# GimmeSoul.net
KiCad netlist of a schematic drawn in EAGLE
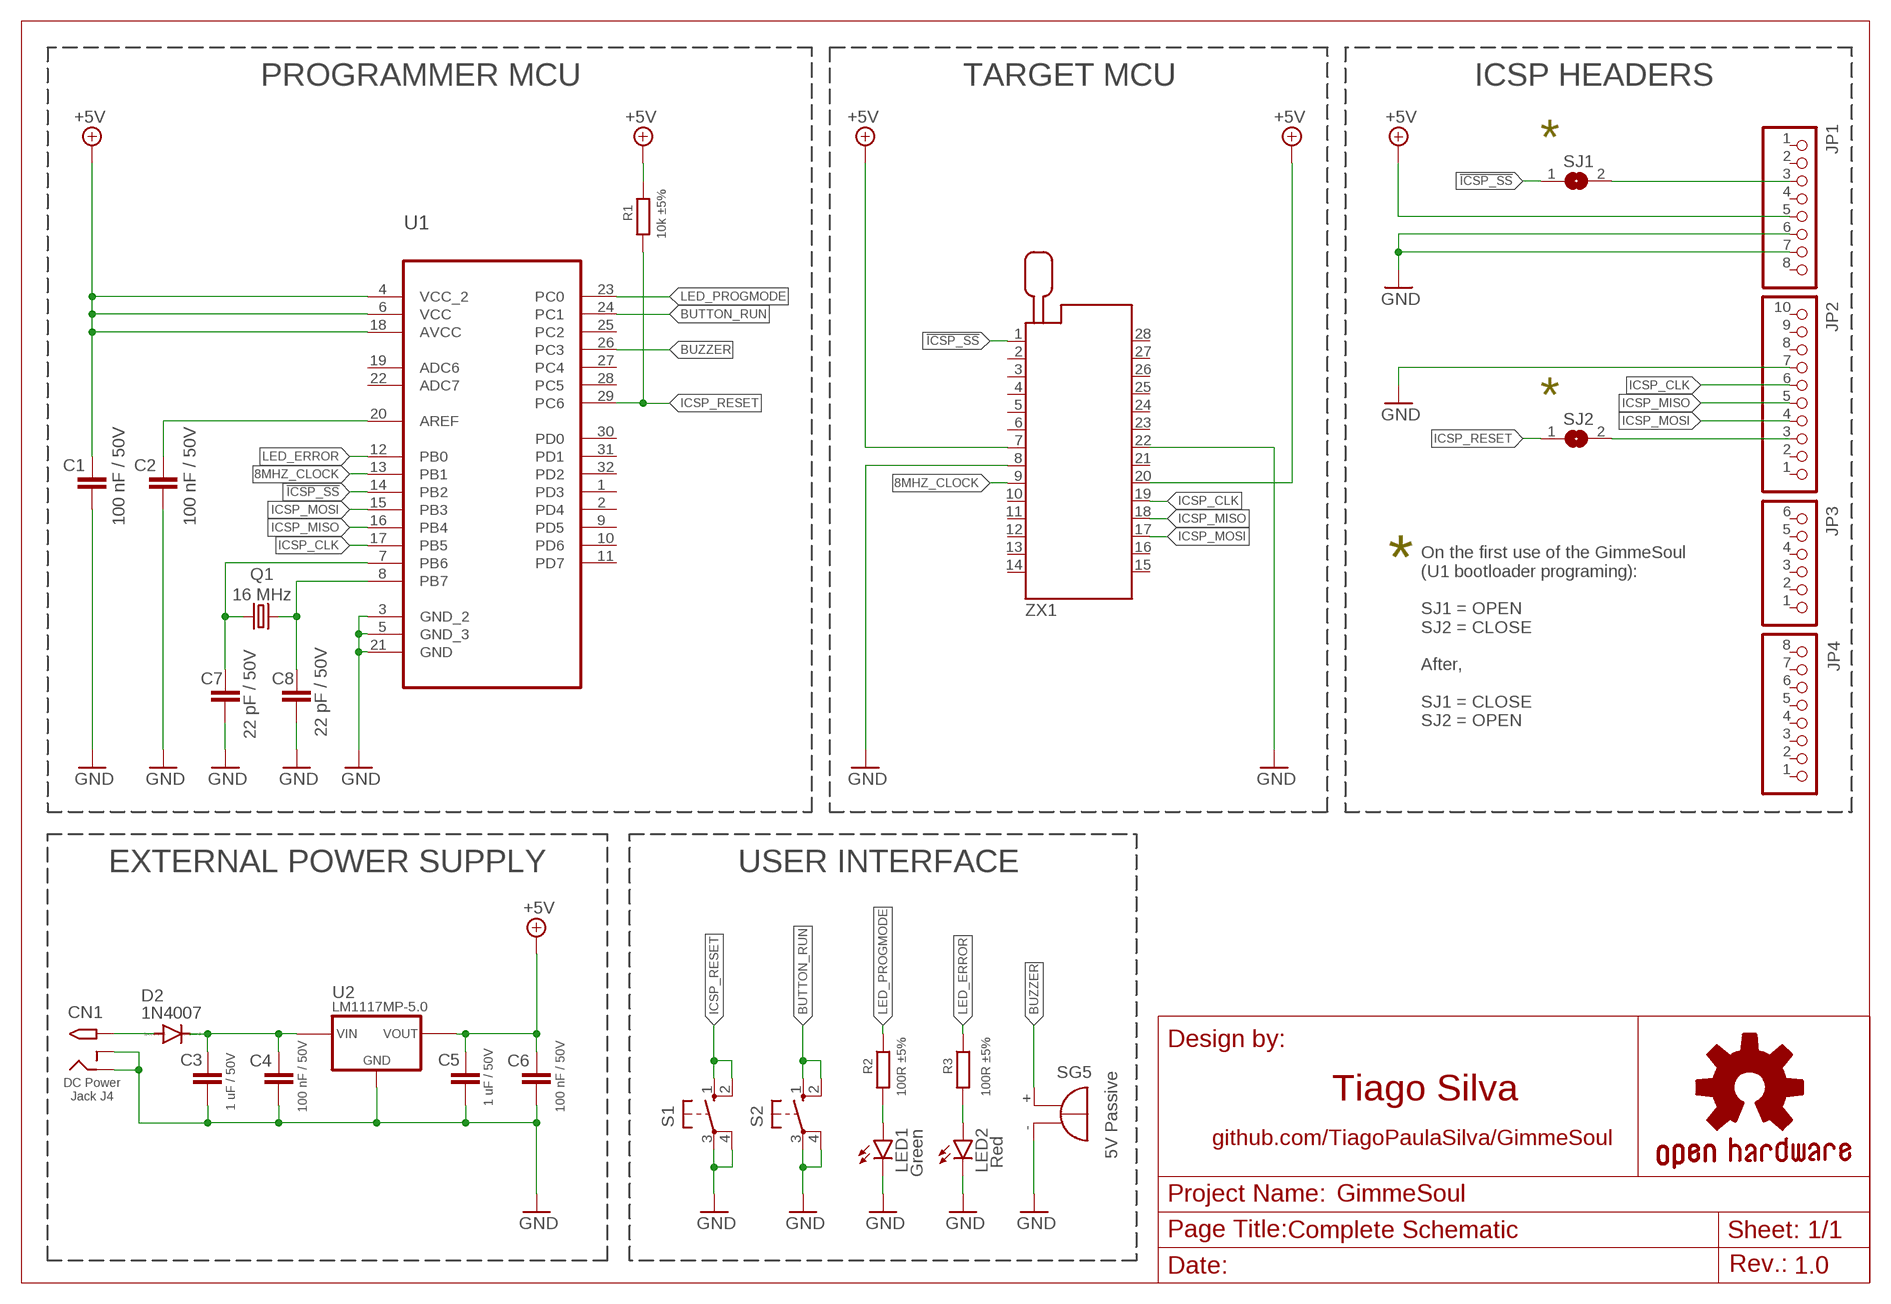
[diagram p0: schematic, sheet 1]

(export (version "E")
  (design (tool "Eeschema 10.0.6"))
  (components
    (comp (ref "C1")
      (value "100 nF / 50V")
      (footprint "eagle-import:C0805")
      (libsource (lib "eagle-import") (part "C-EUC0805"))
    )
    (comp (ref "C2")
      (value "100 nF / 50V")
      (footprint "eagle-import:C0805")
      (libsource (lib "eagle-import") (part "C-EUC0805"))
    )
    (comp (ref "C3")
      (value "1 uF / 50V")
      (footprint "eagle-import:C0805")
      (libsource (lib "eagle-import") (part "C-EUC0805"))
    )
    (comp (ref "C4")
      (value "100 nF / 50V")
      (footprint "eagle-import:C0805")
      (libsource (lib "eagle-import") (part "C-EUC0805"))
    )
    (comp (ref "C5")
      (value "1 uF / 50V")
      (footprint "eagle-import:C0805")
      (libsource (lib "eagle-import") (part "C-EUC0805"))
    )
    (comp (ref "C6")
      (value "100 nF / 50V")
      (footprint "eagle-import:C0805")
      (libsource (lib "eagle-import") (part "C-EUC0805"))
    )
    (comp (ref "C7")
      (value "22 pF / 50V")
      (footprint "eagle-import:C0805")
      (libsource (lib "eagle-import") (part "C-EUC0805"))
    )
    (comp (ref "C8")
      (value "22 pF / 50V")
      (footprint "eagle-import:C0805")
      (libsource (lib "eagle-import") (part "C-EUC0805"))
    )
    (comp (ref "CN1")
      (value "2.1MMJACKTHM")
      (footprint "eagle-import:PJ-102A")
      (libsource (lib "eagle-import") (part "2.1MMJACKTHM"))
    )
    (comp (ref "D2")
      (value "1N4007")
      (footprint "eagle-import:SOD123")
      (libsource (lib "eagle-import") (part "DIODE-SOD123"))
    )
    (comp (ref "JP1")
      (value "PINHD-1X8")
      (footprint "eagle-import:1X08")
      (libsource (lib "eagle-import") (part "PINHD-1X8"))
    )
    (comp (ref "JP2")
      (value "PINHD-1X10_ARD")
      (footprint "eagle-import:1X10")
      (libsource (lib "eagle-import") (part "PINHD-1X10_ARD"))
    )
    (comp (ref "JP3")
      (value "PINHD-1X6")
      (footprint "eagle-import:1X06")
      (libsource (lib "eagle-import") (part "PINHD-1X6"))
    )
    (comp (ref "JP4")
      (value "PINHD-1X8")
      (footprint "eagle-import:1X08")
      (libsource (lib "eagle-import") (part "PINHD-1X8"))
    )
    (comp (ref "LED1")
      (value "Green")
      (footprint "eagle-import:LED5MM")
      (libsource (lib "eagle-import") (part "LED5MM"))
    )
    (comp (ref "LED2")
      (value "Red")
      (footprint "eagle-import:LED5MM")
      (libsource (lib "eagle-import") (part "LED5MM"))
    )
    (comp (ref "Q1")
      (value "16 MHz")
      (footprint "eagle-import:HC49_S")
      (libsource (lib "eagle-import") (part "CRYSTALHC49S"))
    )
    (comp (ref "R1")
      (value "10k ±5%")
      (footprint "eagle-import:R0805")
      (libsource (lib "eagle-import") (part "R-EU_R0805"))
    )
    (comp (ref "R2")
      (value "100R ±5%")
      (footprint "eagle-import:R0805")
      (libsource (lib "eagle-import") (part "R-EU_R0805"))
    )
    (comp (ref "R3")
      (value "100R ±5%")
      (footprint "eagle-import:R0805")
      (libsource (lib "eagle-import") (part "R-EU_R0805"))
    )
    (comp (ref "S1")
      (value "10-XX")
      (footprint "eagle-import:B3F-10XX")
      (fields (field (name "MPN") "B3F-1000"))
      (libsource (lib "eagle-import") (part "10-XX"))
    )
    (comp (ref "S2")
      (value "10-XX")
      (footprint "eagle-import:B3F-10XX")
      (fields (field (name "MPN") "B3F-1000"))
      (libsource (lib "eagle-import") (part "10-XX"))
    )
    (comp (ref "SG5")
      (value "5V Passive")
      (footprint "eagle-import:F_QMBIII")
      (libsource (lib "eagle-import") (part "F/QMBIII"))
    )
    (comp (ref "SJ1") (value "SJ") (footprint "eagle-import:SJ") (libsource (lib "eagle-import") (part "SJ")))
    (comp (ref "SJ2") (value "SJ") (footprint "eagle-import:SJ") (libsource (lib "eagle-import") (part "SJ")))
    (comp (ref "U1")
      (value "ATMEGA328P-AU")
      (footprint "eagle-import:QFP80P900X900X120-32N")
      (libsource (lib "eagle-import") (part "ATMEGA328P-AU"))
    )
    (comp (ref "U2")
      (value "LM1117MP-5.0")
      (footprint "eagle-import:SOT223")
      (fields (field (name "MF") "Texas Instruments") (field (name "MP") "REG1117"))
      (libsource (lib "eagle-import") (part "REG1117"))
    )
    (comp (ref "ZX1")
      (value "228-4817-00-0602J")
      (footprint "eagle-import:228-4817-00-0602J")
      (fields (field (name "MF") "3M"))
      (libsource (lib "eagle-import") (part "228-?00-0602J4817-"))
    )
  )
  (nets
    (net (code "1") (name "+5V") (class "Default")
      (node (ref "C1") (pin "2") (pinfunction "2_2") (pintype "passive"))
      (node (ref "C5") (pin "1") (pinfunction "1_1") (pintype "passive"))
      (node (ref "C6") (pin "1") (pinfunction "1_1") (pintype "passive"))
      (node (ref "JP1") (pin "5") (pinfunction "5_5") (pintype "passive"))
      (node (ref "R1") (pin "1") (pinfunction "1_1") (pintype "passive"))
      (node (ref "U1") (pin "18") (pinfunction "AVCC_18") (pintype "power_in"))
      (node (ref "U1") (pin "4") (pinfunction "VCC_2_4") (pintype "power_in"))
      (node (ref "U1") (pin "6") (pinfunction "VCC_6") (pintype "power_in"))
      (node (ref "U2") (pin "2") (pinfunction "VOUT_2") (pintype "output"))
      (node (ref "U2") (pin "4") (pinfunction "VOUT_4") (pintype "output"))
      (node (ref "ZX1") (pin "20") (pinfunction "20_20") (pintype "passive"))
      (node (ref "ZX1") (pin "7") (pinfunction "7_7") (pintype "passive"))
    )
    (net (code "2") (name "/~{ICSP_SS}") (class "Default")
      (node (ref "SJ1") (pin "1") (pinfunction "1_1") (pintype "passive"))
      (node (ref "U1") (pin "14") (pinfunction "PB2_14") (pintype "bidirectional"))
      (node (ref "ZX1") (pin "1") (pinfunction "1_1") (pintype "passive"))
    )
    (net (code "3") (name "8MHZ_CLOCK") (class "Default")
      (node (ref "U1") (pin "13") (pinfunction "PB1_13") (pintype "bidirectional"))
      (node (ref "ZX1") (pin "9") (pinfunction "9_9") (pintype "passive"))
    )
    (net (code "4") (name "BUTTON_RUN") (class "Default")
      (node (ref "S2") (pin "1") (pinfunction "S_1") (pintype "passive"))
      (node (ref "S2") (pin "2") (pinfunction "S1_2") (pintype "passive"))
      (node (ref "U1") (pin "24") (pinfunction "PC1_24") (pintype "bidirectional"))
    )
    (net (code "5") (name "BUZZER") (class "Default")
      (node (ref "SG5") (pin "+") (pinfunction "-_+") (pintype "passive"))
      (node (ref "U1") (pin "26") (pinfunction "PC3_26") (pintype "bidirectional"))
    )
    (net (code "6") (name "GND") (class "Default")
      (node (ref "C1") (pin "1") (pinfunction "1_1") (pintype "passive"))
      (node (ref "C2") (pin "1") (pinfunction "1_1") (pintype "passive"))
      (node (ref "C3") (pin "2") (pinfunction "2_2") (pintype "passive"))
      (node (ref "C4") (pin "2") (pinfunction "2_2") (pintype "passive"))
      (node (ref "C5") (pin "2") (pinfunction "2_2") (pintype "passive"))
      (node (ref "C6") (pin "2") (pinfunction "2_2") (pintype "passive"))
      (node (ref "C7") (pin "1") (pinfunction "1_1") (pintype "passive"))
      (node (ref "C8") (pin "1") (pinfunction "1_1") (pintype "passive"))
      (node (ref "CN1") (pin "RING") (pinfunction "RING_RING") (pintype "bidirectional"))
      (node (ref "CN1") (pin "RING_SW") (pinfunction "RING_SW_RING_SW") (pintype "bidirectional"))
      (node (ref "JP1") (pin "6") (pinfunction "6_6") (pintype "passive"))
      (node (ref "JP1") (pin "7") (pinfunction "7_7") (pintype "passive"))
      (node (ref "JP2") (pin "7") (pinfunction "7_7") (pintype "passive"))
      (node (ref "LED1") (pin "K") (pinfunction "C_K") (pintype "passive"))
      (node (ref "LED2") (pin "K") (pinfunction "C_K") (pintype "passive"))
      (node (ref "S1") (pin "3") (pinfunction "P_3") (pintype "passive"))
      (node (ref "S1") (pin "4") (pinfunction "P1_4") (pintype "passive"))
      (node (ref "S2") (pin "3") (pinfunction "P_3") (pintype "passive"))
      (node (ref "S2") (pin "4") (pinfunction "P1_4") (pintype "passive"))
      (node (ref "SG5") (pin "-") (pinfunction "+_-") (pintype "passive"))
      (node (ref "U1") (pin "21") (pinfunction "GND_21") (pintype "passive"))
      (node (ref "U1") (pin "3") (pinfunction "GND_2_3") (pintype "passive"))
      (node (ref "U1") (pin "5") (pinfunction "GND_3_5") (pintype "passive"))
      (node (ref "U2") (pin "1") (pinfunction "GND_1") (pintype "power_in"))
      (node (ref "ZX1") (pin "22") (pinfunction "22_22") (pintype "passive"))
      (node (ref "ZX1") (pin "8") (pinfunction "8_8") (pintype "passive"))
    )
    (net (code "7") (name "ICSP_CLK") (class "Default")
      (node (ref "JP2") (pin "6") (pinfunction "6_6") (pintype "passive"))
      (node (ref "U1") (pin "17") (pinfunction "PB5_17") (pintype "bidirectional"))
      (node (ref "ZX1") (pin "19") (pinfunction "19_19") (pintype "passive"))
    )
    (net (code "8") (name "ICSP_MISO") (class "Default")
      (node (ref "JP2") (pin "5") (pinfunction "5_5") (pintype "passive"))
      (node (ref "U1") (pin "16") (pinfunction "PB4_16") (pintype "bidirectional"))
      (node (ref "ZX1") (pin "18") (pinfunction "18_18") (pintype "passive"))
    )
    (net (code "9") (name "ICSP_MOSI") (class "Default")
      (node (ref "JP2") (pin "4") (pinfunction "4_4") (pintype "passive"))
      (node (ref "U1") (pin "15") (pinfunction "PB3_15") (pintype "bidirectional"))
      (node (ref "ZX1") (pin "17") (pinfunction "17_17") (pintype "passive"))
    )
    (net (code "10") (name "ICSP_RESET") (class "Default")
      (node (ref "R1") (pin "2") (pinfunction "2_2") (pintype "passive"))
      (node (ref "S1") (pin "1") (pinfunction "S_1") (pintype "passive"))
      (node (ref "S1") (pin "2") (pinfunction "S1_2") (pintype "passive"))
      (node (ref "SJ2") (pin "1") (pinfunction "1_1") (pintype "passive"))
      (node (ref "U1") (pin "29") (pinfunction "PC6_29") (pintype "bidirectional"))
    )
    (net (code "11") (name "LED_ERROR") (class "Default")
      (node (ref "R3") (pin "1") (pinfunction "1_1") (pintype "passive"))
      (node (ref "U1") (pin "12") (pinfunction "PB0_12") (pintype "bidirectional"))
    )
    (net (code "12") (name "LED_PROGMODE") (class "Default")
      (node (ref "R2") (pin "1") (pinfunction "1_1") (pintype "passive"))
      (node (ref "U1") (pin "23") (pinfunction "PC0_23") (pintype "bidirectional"))
    )
    (net (code "13") (name "Net-(CN1-PadTIP)") (class "Default")
      (node (ref "CN1") (pin "TIP") (pinfunction "TIP_TIP") (pintype "bidirectional"))
      (node (ref "D2") (pin "A") (pinfunction "A_A") (pintype "passive"))
    )
    (net (code "14") (name "Net-(JP1-Pad3)") (class "Default")
      (node (ref "JP1") (pin "3") (pinfunction "3_3") (pintype "passive"))
      (node (ref "SJ1") (pin "2") (pinfunction "2_2") (pintype "passive"))
    )
    (net (code "15") (name "Net-(JP2-Pad3)") (class "Default")
      (node (ref "JP2") (pin "3") (pinfunction "3_3") (pintype "passive"))
      (node (ref "SJ2") (pin "2") (pinfunction "2_2") (pintype "passive"))
    )
    (net (code "16") (name "Net-(LED1-PadA)") (class "Default")
      (node (ref "LED1") (pin "A") (pinfunction "A_A") (pintype "passive"))
      (node (ref "R2") (pin "2") (pinfunction "2_2") (pintype "passive"))
    )
    (net (code "17") (name "Net-(LED2-PadA)") (class "Default")
      (node (ref "LED2") (pin "A") (pinfunction "A_A") (pintype "passive"))
      (node (ref "R3") (pin "2") (pinfunction "2_2") (pintype "passive"))
    )
    (net (code "18") (name "Net-(U1-AREF)") (class "Default")
      (node (ref "C2") (pin "2") (pinfunction "2_2") (pintype "passive"))
      (node (ref "U1") (pin "20") (pinfunction "AREF_20") (pintype "input"))
    )
    (net (code "19") (name "Net-(U1-PB6)") (class "Default")
      (node (ref "C7") (pin "2") (pinfunction "2_2") (pintype "passive"))
      (node (ref "Q1") (pin "1") (pinfunction "1_1") (pintype "passive"))
      (node (ref "U1") (pin "7") (pinfunction "PB6_7") (pintype "bidirectional"))
    )
    (net (code "20") (name "Net-(U1-PB7)") (class "Default")
      (node (ref "C8") (pin "2") (pinfunction "2_2") (pintype "passive"))
      (node (ref "Q1") (pin "2") (pinfunction "2_2") (pintype "passive"))
      (node (ref "U1") (pin "8") (pinfunction "PB7_8") (pintype "bidirectional"))
    )
    (net (code "21") (name "Net-(U2-VIN)") (class "Default")
      (node (ref "C3") (pin "1") (pinfunction "1_1") (pintype "passive"))
      (node (ref "C4") (pin "1") (pinfunction "1_1") (pintype "passive"))
      (node (ref "D2") (pin "C") (pinfunction "C_C") (pintype "passive"))
      (node (ref "U2") (pin "3") (pinfunction "VIN_3") (pintype "input"))
    )
    (net (code "22") (name "unconnected-(JP1-Pad1)") (class "Default")
      (node (ref "JP1") (pin "1") (pinfunction "1_1") (pintype "passive"))
    )
    (net (code "23") (name "unconnected-(JP1-Pad2)") (class "Default")
      (node (ref "JP1") (pin "2") (pinfunction "2_2") (pintype "passive"))
    )
    (net (code "24") (name "unconnected-(JP1-Pad4)") (class "Default")
      (node (ref "JP1") (pin "4") (pinfunction "4_4") (pintype "passive"))
    )
    (net (code "25") (name "unconnected-(JP1-Pad8)") (class "Default")
      (node (ref "JP1") (pin "8") (pinfunction "8_8") (pintype "passive"))
    )
    (net (code "26") (name "unconnected-(JP2-Pad1)") (class "Default")
      (node (ref "JP2") (pin "1") (pinfunction "1_1") (pintype "passive"))
    )
    (net (code "27") (name "unconnected-(JP2-Pad2)") (class "Default")
      (node (ref "JP2") (pin "2") (pinfunction "2_2") (pintype "passive"))
    )
    (net (code "28") (name "unconnected-(JP2-Pad8)") (class "Default")
      (node (ref "JP2") (pin "8") (pinfunction "8_8") (pintype "passive"))
    )
    (net (code "29") (name "unconnected-(JP2-Pad9)") (class "Default")
      (node (ref "JP2") (pin "9") (pinfunction "9_9") (pintype "passive"))
    )
    (net (code "30") (name "unconnected-(JP2-Pad10)") (class "Default")
      (node (ref "JP2") (pin "10") (pinfunction "10_10") (pintype "passive"))
    )
    (net (code "31") (name "unconnected-(JP3-Pad1)") (class "Default")
      (node (ref "JP3") (pin "1") (pinfunction "1_1") (pintype "passive"))
    )
    (net (code "32") (name "unconnected-(JP3-Pad2)") (class "Default")
      (node (ref "JP3") (pin "2") (pinfunction "2_2") (pintype "passive"))
    )
    (net (code "33") (name "unconnected-(JP3-Pad3)") (class "Default")
      (node (ref "JP3") (pin "3") (pinfunction "3_3") (pintype "passive"))
    )
    (net (code "34") (name "unconnected-(JP3-Pad4)") (class "Default")
      (node (ref "JP3") (pin "4") (pinfunction "4_4") (pintype "passive"))
    )
    (net (code "35") (name "unconnected-(JP3-Pad5)") (class "Default")
      (node (ref "JP3") (pin "5") (pinfunction "5_5") (pintype "passive"))
    )
    (net (code "36") (name "unconnected-(JP3-Pad6)") (class "Default")
      (node (ref "JP3") (pin "6") (pinfunction "6_6") (pintype "passive"))
    )
    (net (code "37") (name "unconnected-(JP4-Pad1)") (class "Default")
      (node (ref "JP4") (pin "1") (pinfunction "1_1") (pintype "passive"))
    )
    (net (code "38") (name "unconnected-(JP4-Pad2)") (class "Default")
      (node (ref "JP4") (pin "2") (pinfunction "2_2") (pintype "passive"))
    )
    (net (code "39") (name "unconnected-(JP4-Pad3)") (class "Default")
      (node (ref "JP4") (pin "3") (pinfunction "3_3") (pintype "passive"))
    )
    (net (code "40") (name "unconnected-(JP4-Pad4)") (class "Default")
      (node (ref "JP4") (pin "4") (pinfunction "4_4") (pintype "passive"))
    )
    (net (code "41") (name "unconnected-(JP4-Pad5)") (class "Default")
      (node (ref "JP4") (pin "5") (pinfunction "5_5") (pintype "passive"))
    )
    (net (code "42") (name "unconnected-(JP4-Pad6)") (class "Default")
      (node (ref "JP4") (pin "6") (pinfunction "6_6") (pintype "passive"))
    )
    (net (code "43") (name "unconnected-(JP4-Pad7)") (class "Default")
      (node (ref "JP4") (pin "7") (pinfunction "7_7") (pintype "passive"))
    )
    (net (code "44") (name "unconnected-(JP4-Pad8)") (class "Default")
      (node (ref "JP4") (pin "8") (pinfunction "8_8") (pintype "passive"))
    )
    (net (code "45") (name "unconnected-(U1-ADC6-Pad19)") (class "Default")
      (node (ref "U1") (pin "19") (pinfunction "ADC6_19") (pintype "input"))
    )
    (net (code "46") (name "unconnected-(U1-ADC7-Pad22)") (class "Default")
      (node (ref "U1") (pin "22") (pinfunction "ADC7_22") (pintype "input"))
    )
    (net (code "47") (name "unconnected-(U1-PC2-Pad25)") (class "Default")
      (node (ref "U1") (pin "25") (pinfunction "PC2_25") (pintype "bidirectional"))
    )
    (net (code "48") (name "unconnected-(U1-PC4-Pad27)") (class "Default")
      (node (ref "U1") (pin "27") (pinfunction "PC4_27") (pintype "bidirectional"))
    )
    (net (code "49") (name "unconnected-(U1-PC5-Pad28)") (class "Default")
      (node (ref "U1") (pin "28") (pinfunction "PC5_28") (pintype "bidirectional"))
    )
    (net (code "50") (name "unconnected-(U1-PD0-Pad30)") (class "Default")
      (node (ref "U1") (pin "30") (pinfunction "PD0_30") (pintype "bidirectional"))
    )
    (net (code "51") (name "unconnected-(U1-PD1-Pad31)") (class "Default")
      (node (ref "U1") (pin "31") (pinfunction "PD1_31") (pintype "bidirectional"))
    )
    (net (code "52") (name "unconnected-(U1-PD2-Pad32)") (class "Default")
      (node (ref "U1") (pin "32") (pinfunction "PD2_32") (pintype "bidirectional"))
    )
    (net (code "53") (name "unconnected-(U1-PD3-Pad1)") (class "Default")
      (node (ref "U1") (pin "1") (pinfunction "PD3_1") (pintype "bidirectional"))
    )
    (net (code "54") (name "unconnected-(U1-PD4-Pad2)") (class "Default")
      (node (ref "U1") (pin "2") (pinfunction "PD4_2") (pintype "bidirectional"))
    )
    (net (code "55") (name "unconnected-(U1-PD5-Pad9)") (class "Default")
      (node (ref "U1") (pin "9") (pinfunction "PD5_9") (pintype "bidirectional"))
    )
    (net (code "56") (name "unconnected-(U1-PD6-Pad10)") (class "Default")
      (node (ref "U1") (pin "10") (pinfunction "PD6_10") (pintype "bidirectional"))
    )
    (net (code "57") (name "unconnected-(U1-PD7-Pad11)") (class "Default")
      (node (ref "U1") (pin "11") (pinfunction "PD7_11") (pintype "bidirectional"))
    )
    (net (code "58") (name "unconnected-(ZX1-Pad2)") (class "Default")
      (node (ref "ZX1") (pin "2") (pinfunction "2_2") (pintype "passive"))
    )
    (net (code "59") (name "unconnected-(ZX1-Pad3)") (class "Default")
      (node (ref "ZX1") (pin "3") (pinfunction "3_3") (pintype "passive"))
    )
    (net (code "60") (name "unconnected-(ZX1-Pad4)") (class "Default")
      (node (ref "ZX1") (pin "4") (pinfunction "4_4") (pintype "passive"))
    )
    (net (code "61") (name "unconnected-(ZX1-Pad5)") (class "Default")
      (node (ref "ZX1") (pin "5") (pinfunction "5_5") (pintype "passive"))
    )
    (net (code "62") (name "unconnected-(ZX1-Pad6)") (class "Default")
      (node (ref "ZX1") (pin "6") (pinfunction "6_6") (pintype "passive"))
    )
    (net (code "63") (name "unconnected-(ZX1-Pad10)") (class "Default")
      (node (ref "ZX1") (pin "10") (pinfunction "10_10") (pintype "passive"))
    )
    (net (code "64") (name "unconnected-(ZX1-Pad11)") (class "Default")
      (node (ref "ZX1") (pin "11") (pinfunction "11_11") (pintype "passive"))
    )
    (net (code "65") (name "unconnected-(ZX1-Pad12)") (class "Default")
      (node (ref "ZX1") (pin "12") (pinfunction "12_12") (pintype "passive"))
    )
    (net (code "66") (name "unconnected-(ZX1-Pad13)") (class "Default")
      (node (ref "ZX1") (pin "13") (pinfunction "13_13") (pintype "passive"))
    )
    (net (code "67") (name "unconnected-(ZX1-Pad14)") (class "Default")
      (node (ref "ZX1") (pin "14") (pinfunction "14_14") (pintype "passive"))
    )
    (net (code "68") (name "unconnected-(ZX1-Pad15)") (class "Default")
      (node (ref "ZX1") (pin "15") (pinfunction "15_15") (pintype "passive"))
    )
    (net (code "69") (name "unconnected-(ZX1-Pad16)") (class "Default")
      (node (ref "ZX1") (pin "16") (pinfunction "16_16") (pintype "passive"))
    )
    (net (code "70") (name "unconnected-(ZX1-Pad21)") (class "Default")
      (node (ref "ZX1") (pin "21") (pinfunction "21_21") (pintype "passive"))
    )
    (net (code "71") (name "unconnected-(ZX1-Pad23)") (class "Default")
      (node (ref "ZX1") (pin "23") (pinfunction "23_23") (pintype "passive"))
    )
    (net (code "72") (name "unconnected-(ZX1-Pad24)") (class "Default")
      (node (ref "ZX1") (pin "24") (pinfunction "24_24") (pintype "passive"))
    )
    (net (code "73") (name "unconnected-(ZX1-Pad25)") (class "Default")
      (node (ref "ZX1") (pin "25") (pinfunction "25_25") (pintype "passive"))
    )
    (net (code "74") (name "unconnected-(ZX1-Pad26)") (class "Default")
      (node (ref "ZX1") (pin "26") (pinfunction "26_26") (pintype "passive"))
    )
    (net (code "75") (name "unconnected-(ZX1-Pad27)") (class "Default")
      (node (ref "ZX1") (pin "27") (pinfunction "27_27") (pintype "passive"))
    )
    (net (code "76") (name "unconnected-(ZX1-Pad28)") (class "Default")
      (node (ref "ZX1") (pin "28") (pinfunction "28_28") (pintype "passive"))
    )
  )
)
